# dualinv.net
KiCad netlist of a schematic drawn in Altium Designer
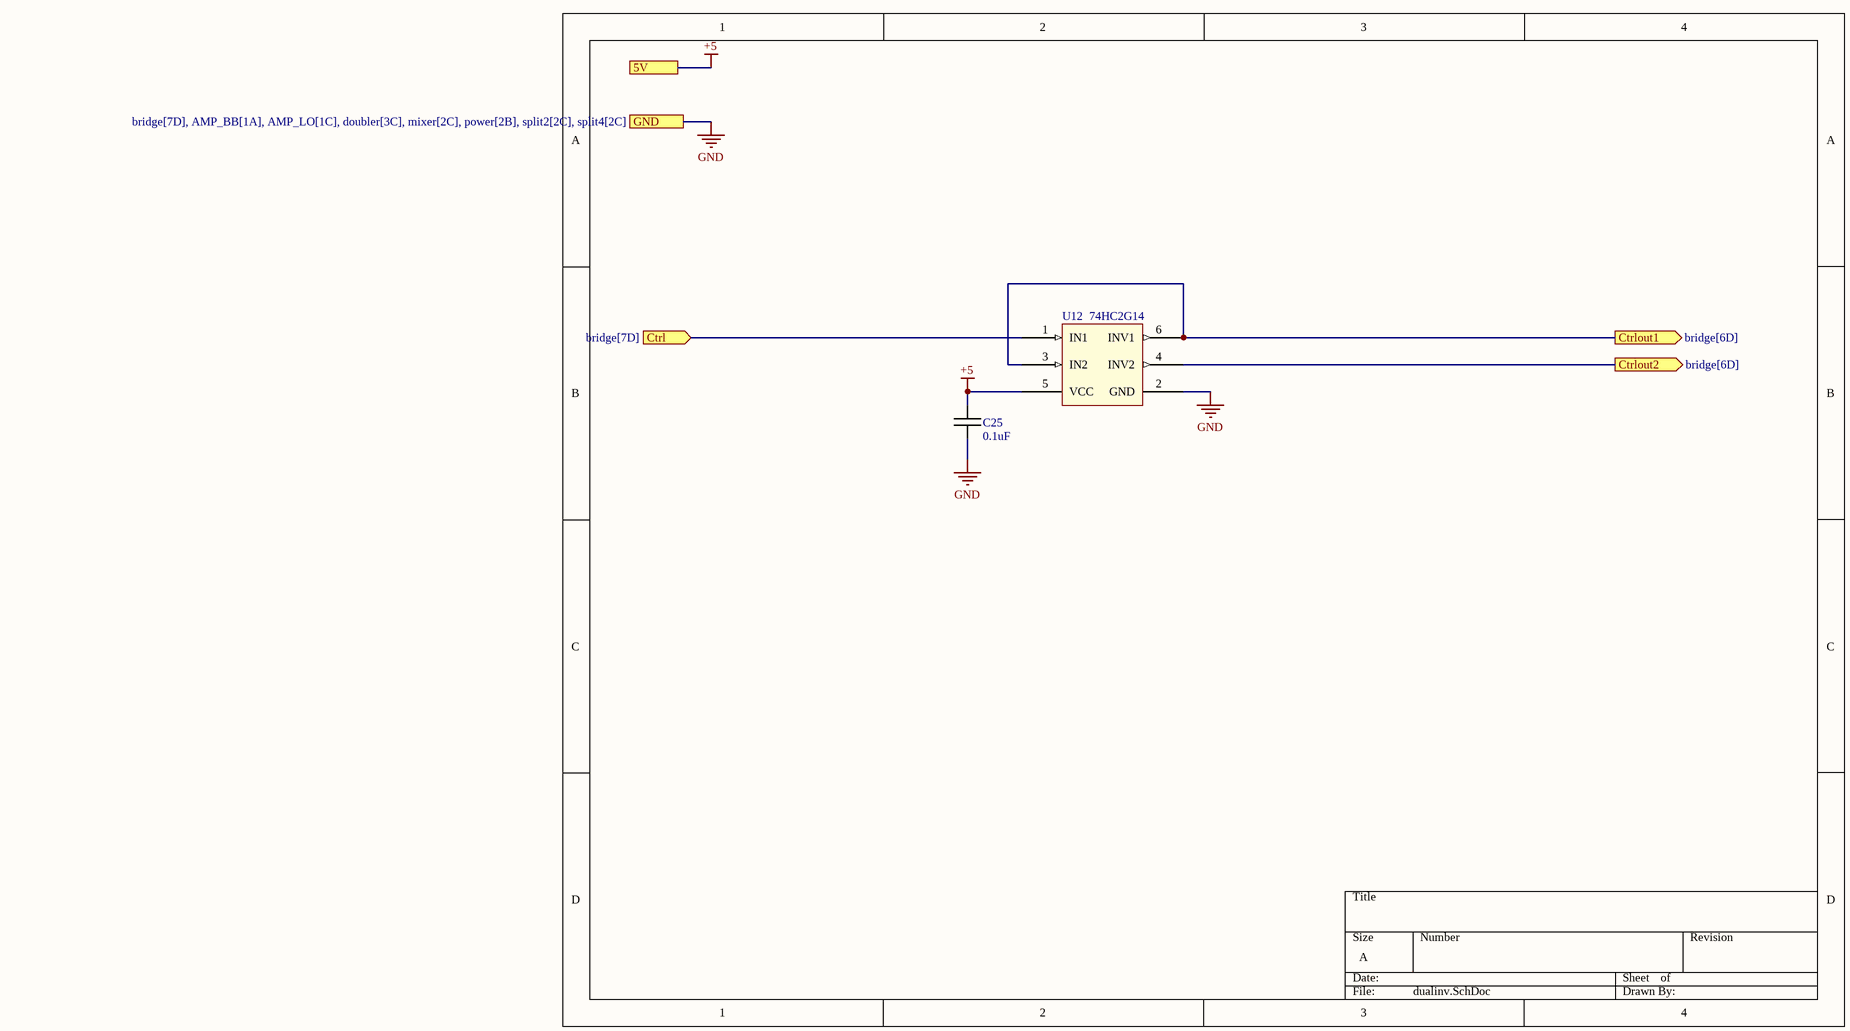
[diagram p0: dualinv.SchDoc]

(export (version "E")
  (design (tool "Eeschema 10.0.6"))
  (components
    (comp (ref "C25")
      (value "0.1uF")
      (footprint "CAPC1608X90N")
      (description "SMD Capacitor X8L(MURATA) with Capacitance: 0.10uF Tol. 10%. Rated Voltage: 50Vdc")
      (fields (field (name "MANUFACTURER") "Murata") (field (name "PART NUMBER") "GCM188L81H104KA57D"))
      (libsource (lib "LCR") (part "GCM188L81H104KA57D"))
    )
    (comp (ref "U12")
      (value "74HC2G14")
      (footprint "TSOP-6")
      (description "Inverters Dual inverting Schmitt trigger, 2CH")
      (fields (field (name "PART NUMBER") "74HC2G14GV") (field (name "MANUFACTURER") "Nexperia"))
      (libsource (lib "FullyDigital") (part "74HC2G14"))
    )
  )
  (nets
    (net (code "1") (name "+5") (class "Default")
      (node (ref "C25") (pin "2") (pinfunction "2_2") (pintype "passive"))
      (node (ref "U12") (pin "5") (pinfunction "VCC_5") (pintype "power_in"))
    )
    (net (code "2") (name "/Ctrl") (class "Default")
      (node (ref "U12") (pin "1") (pinfunction "IN1_1") (pintype "input"))
    )
    (net (code "3") (name "/Ctrlout1") (class "Default")
      (node (ref "U12") (pin "3") (pinfunction "IN2_3") (pintype "input"))
      (node (ref "U12") (pin "6") (pinfunction "INV1_6") (pintype "output"))
    )
    (net (code "4") (name "/Ctrlout2") (class "Default")
      (node (ref "U12") (pin "4") (pinfunction "INV2_4") (pintype "output"))
    )
    (net (code "5") (name "GND") (class "Default")
      (node (ref "C25") (pin "1") (pinfunction "1_1") (pintype "passive"))
      (node (ref "U12") (pin "2") (pinfunction "GND_2") (pintype "passive"))
    )
  )
)
